# sx3_breakout.net
KiCad netlist of a schematic drawn in EAGLE
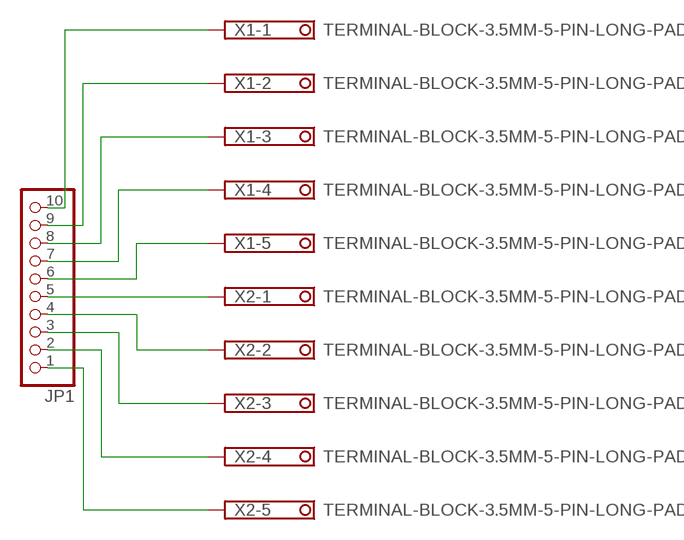
[diagram p0: schematic, sheet 1]

(export (version "E")
  (design (tool "Eeschema 10.0.6"))
  (components
    (comp (ref "JP1")
      (value "PINHD-1X10")
      (footprint "eagle-import:1X10")
      (libsource (lib "eagle-import") (part "PINHD-1X10"))
    )
    (comp (ref "X1")
      (value "TERMINAL-BLOCK-3.5MM-5-PIN-LONG-PAD")
      (footprint "eagle-import:TERMINAL-BLOCK-5-PIN-3.5MM-LONG-PAD")
      (libsource (lib "eagle-import") (part "TERMINAL-BLOCK-3.5MM-5-PIN-LONG-PAD"))
    )
    (comp (ref "X2")
      (value "TERMINAL-BLOCK-3.5MM-5-PIN-LONG-PAD")
      (footprint "eagle-import:TERMINAL-BLOCK-5-PIN-3.5MM-LONG-PAD")
      (libsource (lib "eagle-import") (part "TERMINAL-BLOCK-3.5MM-5-PIN-LONG-PAD"))
    )
  )
  (nets
    (net (code "1") (name "Net-(X1A-K)") (class "Default")
      (node (ref "JP1") (pin "10") (pinfunction "10_10") (pintype "passive"))
      (node (ref "X1") (pin "1") (pinfunction "K_1") (pintype "passive"))
    )
    (net (code "2") (name "Net-(X1B-K)") (class "Default")
      (node (ref "JP1") (pin "9") (pinfunction "9_9") (pintype "passive"))
      (node (ref "X1") (pin "2") (pinfunction "K_2") (pintype "passive"))
    )
    (net (code "3") (name "Net-(X1C-K)") (class "Default")
      (node (ref "JP1") (pin "8") (pinfunction "8_8") (pintype "passive"))
      (node (ref "X1") (pin "3") (pinfunction "K_3") (pintype "passive"))
    )
    (net (code "4") (name "Net-(X1D-K)") (class "Default")
      (node (ref "JP1") (pin "7") (pinfunction "7_7") (pintype "passive"))
      (node (ref "X1") (pin "4") (pinfunction "K_4") (pintype "passive"))
    )
    (net (code "5") (name "Net-(X1E-K)") (class "Default")
      (node (ref "JP1") (pin "6") (pinfunction "6_6") (pintype "passive"))
      (node (ref "X1") (pin "5") (pinfunction "K_5") (pintype "passive"))
    )
    (net (code "6") (name "Net-(X2A-K)") (class "Default")
      (node (ref "JP1") (pin "5") (pinfunction "5_5") (pintype "passive"))
      (node (ref "X2") (pin "1") (pinfunction "K_1") (pintype "passive"))
    )
    (net (code "7") (name "Net-(X2B-K)") (class "Default")
      (node (ref "JP1") (pin "4") (pinfunction "4_4") (pintype "passive"))
      (node (ref "X2") (pin "2") (pinfunction "K_2") (pintype "passive"))
    )
    (net (code "8") (name "Net-(X2C-K)") (class "Default")
      (node (ref "JP1") (pin "3") (pinfunction "3_3") (pintype "passive"))
      (node (ref "X2") (pin "3") (pinfunction "K_3") (pintype "passive"))
    )
    (net (code "9") (name "Net-(X2D-K)") (class "Default")
      (node (ref "JP1") (pin "2") (pinfunction "2_2") (pintype "passive"))
      (node (ref "X2") (pin "4") (pinfunction "K_4") (pintype "passive"))
    )
    (net (code "10") (name "Net-(X2E-K)") (class "Default")
      (node (ref "JP1") (pin "1") (pinfunction "1_1") (pintype "passive"))
      (node (ref "X2") (pin "5") (pinfunction "K_5") (pintype "passive"))
    )
  )
)
